# keyboard.net
KiCad netlist of a schematic drawn in Altium Designer
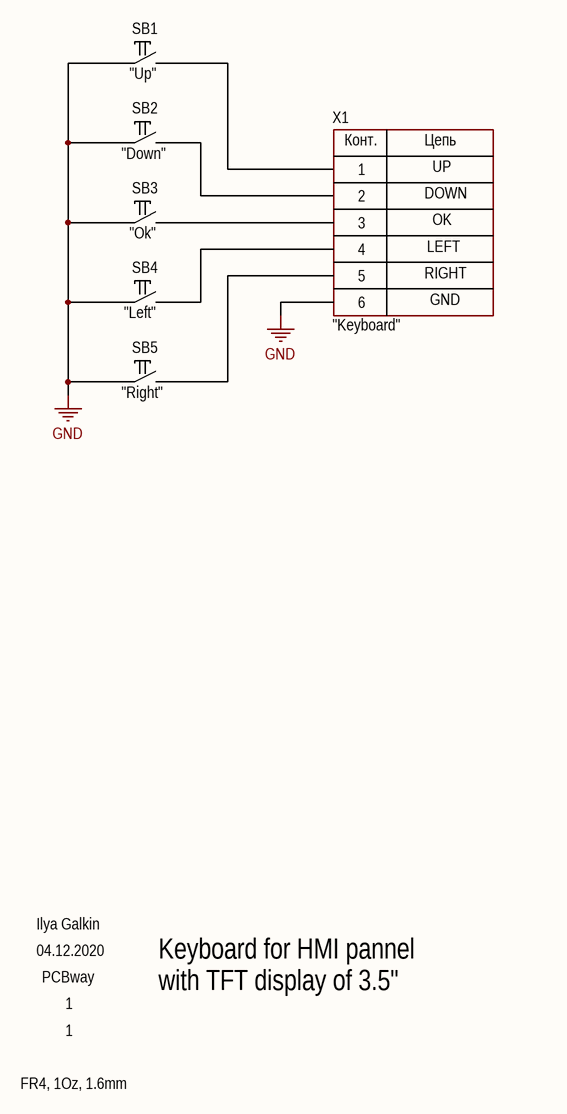
[diagram p0: keyboard.SchDoc]

(export (version "E")
  (design (tool "Eeschema 10.0.6"))
  (components
    (comp (ref "SB1")
      (value "~")
      (footprint "BUT: 6x6")
      (fields
        (field (name "MANUFACTURER") "TE Connectivity")
        (field (name "VALUEMANUFACTURERPARTNUMBER") "Tactile button, 6x6mm")
        (field (name "PARTNUMBER") "FSM2JSMAATR")
        (field (name "COMMENTTEXT") "\"Up\"")
      )
      (libsource (lib "electromechanics") (part "Button_tactile"))
    )
    (comp (ref "SB2")
      (value "~")
      (footprint "BUT: 6x6")
      (fields
        (field (name "MANUFACTURER") "TE Connectivity")
        (field (name "VALUEMANUFACTURERPARTNUMBER") "Tactile button, 6x6mm")
        (field (name "PARTNUMBER") "FSM2JSMAATR")
        (field (name "COMMENTTEXT") "\"Down\"")
      )
      (libsource (lib "electromechanics") (part "Button_tactile"))
    )
    (comp (ref "SB3")
      (value "~")
      (footprint "BUT: 6x6")
      (fields
        (field (name "MANUFACTURER") "TE Connectivity")
        (field (name "VALUEMANUFACTURERPARTNUMBER") "Tactile button, 6x6mm")
        (field (name "PARTNUMBER") "FSM2JSMAATR")
        (field (name "COMMENTTEXT") "\"Ok\"")
      )
      (libsource (lib "electromechanics") (part "Button_tactile"))
    )
    (comp (ref "SB4")
      (value "~")
      (footprint "BUT: 6x6")
      (fields
        (field (name "MANUFACTURER") "TE Connectivity")
        (field (name "VALUEMANUFACTURERPARTNUMBER") "Tactile button, 6x6mm")
        (field (name "PARTNUMBER") "FSM2JSMAATR")
        (field (name "COMMENTTEXT") "\"Left\"")
      )
      (libsource (lib "electromechanics") (part "Button_tactile"))
    )
    (comp (ref "SB5")
      (value "~")
      (footprint "BUT: 6x6")
      (fields
        (field (name "MANUFACTURER") "TE Connectivity")
        (field (name "VALUEMANUFACTURERPARTNUMBER") "Tactile button, 6x6mm")
        (field (name "PARTNUMBER") "FSM2JSMAATR")
        (field (name "COMMENTTEXT") "\"Right\"")
      )
      (libsource (lib "electromechanics") (part "Button_tactile"))
    )
    (comp (ref "X1")
      (value "~")
      (footprint "CON: CWF-6R")
      (fields
        (field (name "MANUFACTURER") "Connfly")
        (field (name "VALUEMANUFACTURERPARTNUMBER") "Connector, 6pin, 2.54mm, 250VAC, 3A")
        (field (name "PARTNUMBER") "CWF-6R")
        (field (name "COMMENTTEXT") "\"Keyboard\"")
      )
      (libsource (lib "connector") (part "CWF-6"))
    )
  )
  (nets
    (net (code "1") (name "GND") (class "Default")
      (node (ref "SB1") (pin "1") (pinfunction "1_1") (pintype "passive"))
      (node (ref "SB2") (pin "1") (pinfunction "1_1") (pintype "passive"))
      (node (ref "SB3") (pin "1") (pinfunction "1_1") (pintype "passive"))
      (node (ref "SB4") (pin "1") (pinfunction "1_1") (pintype "passive"))
      (node (ref "SB5") (pin "1") (pinfunction "1_1") (pintype "passive"))
      (node (ref "X1") (pin "6") (pinfunction "6_6") (pintype "power_in"))
    )
    (net (code "2") (name "Net-(SB1-Pad2)") (class "Default")
      (node (ref "SB1") (pin "2") (pinfunction "2_2") (pintype "passive"))
      (node (ref "X1") (pin "1") (pinfunction "1_1") (pintype "passive"))
    )
    (net (code "3") (name "Net-(SB2-Pad2)") (class "Default")
      (node (ref "SB2") (pin "2") (pinfunction "2_2") (pintype "passive"))
      (node (ref "X1") (pin "2") (pinfunction "2_2") (pintype "passive"))
    )
    (net (code "4") (name "Net-(SB3-Pad2)") (class "Default")
      (node (ref "SB3") (pin "2") (pinfunction "2_2") (pintype "passive"))
      (node (ref "X1") (pin "3") (pinfunction "3_3") (pintype "power_in"))
    )
    (net (code "5") (name "Net-(SB4-Pad2)") (class "Default")
      (node (ref "SB4") (pin "2") (pinfunction "2_2") (pintype "passive"))
      (node (ref "X1") (pin "4") (pinfunction "4_4") (pintype "power_in"))
    )
    (net (code "6") (name "Net-(SB5-Pad2)") (class "Default")
      (node (ref "SB5") (pin "2") (pinfunction "2_2") (pintype "passive"))
      (node (ref "X1") (pin "5") (pinfunction "5_5") (pintype "power_in"))
    )
  )
)
